# sch_microcontroller.net
KiCad netlist of a schematic drawn in EasyEDA
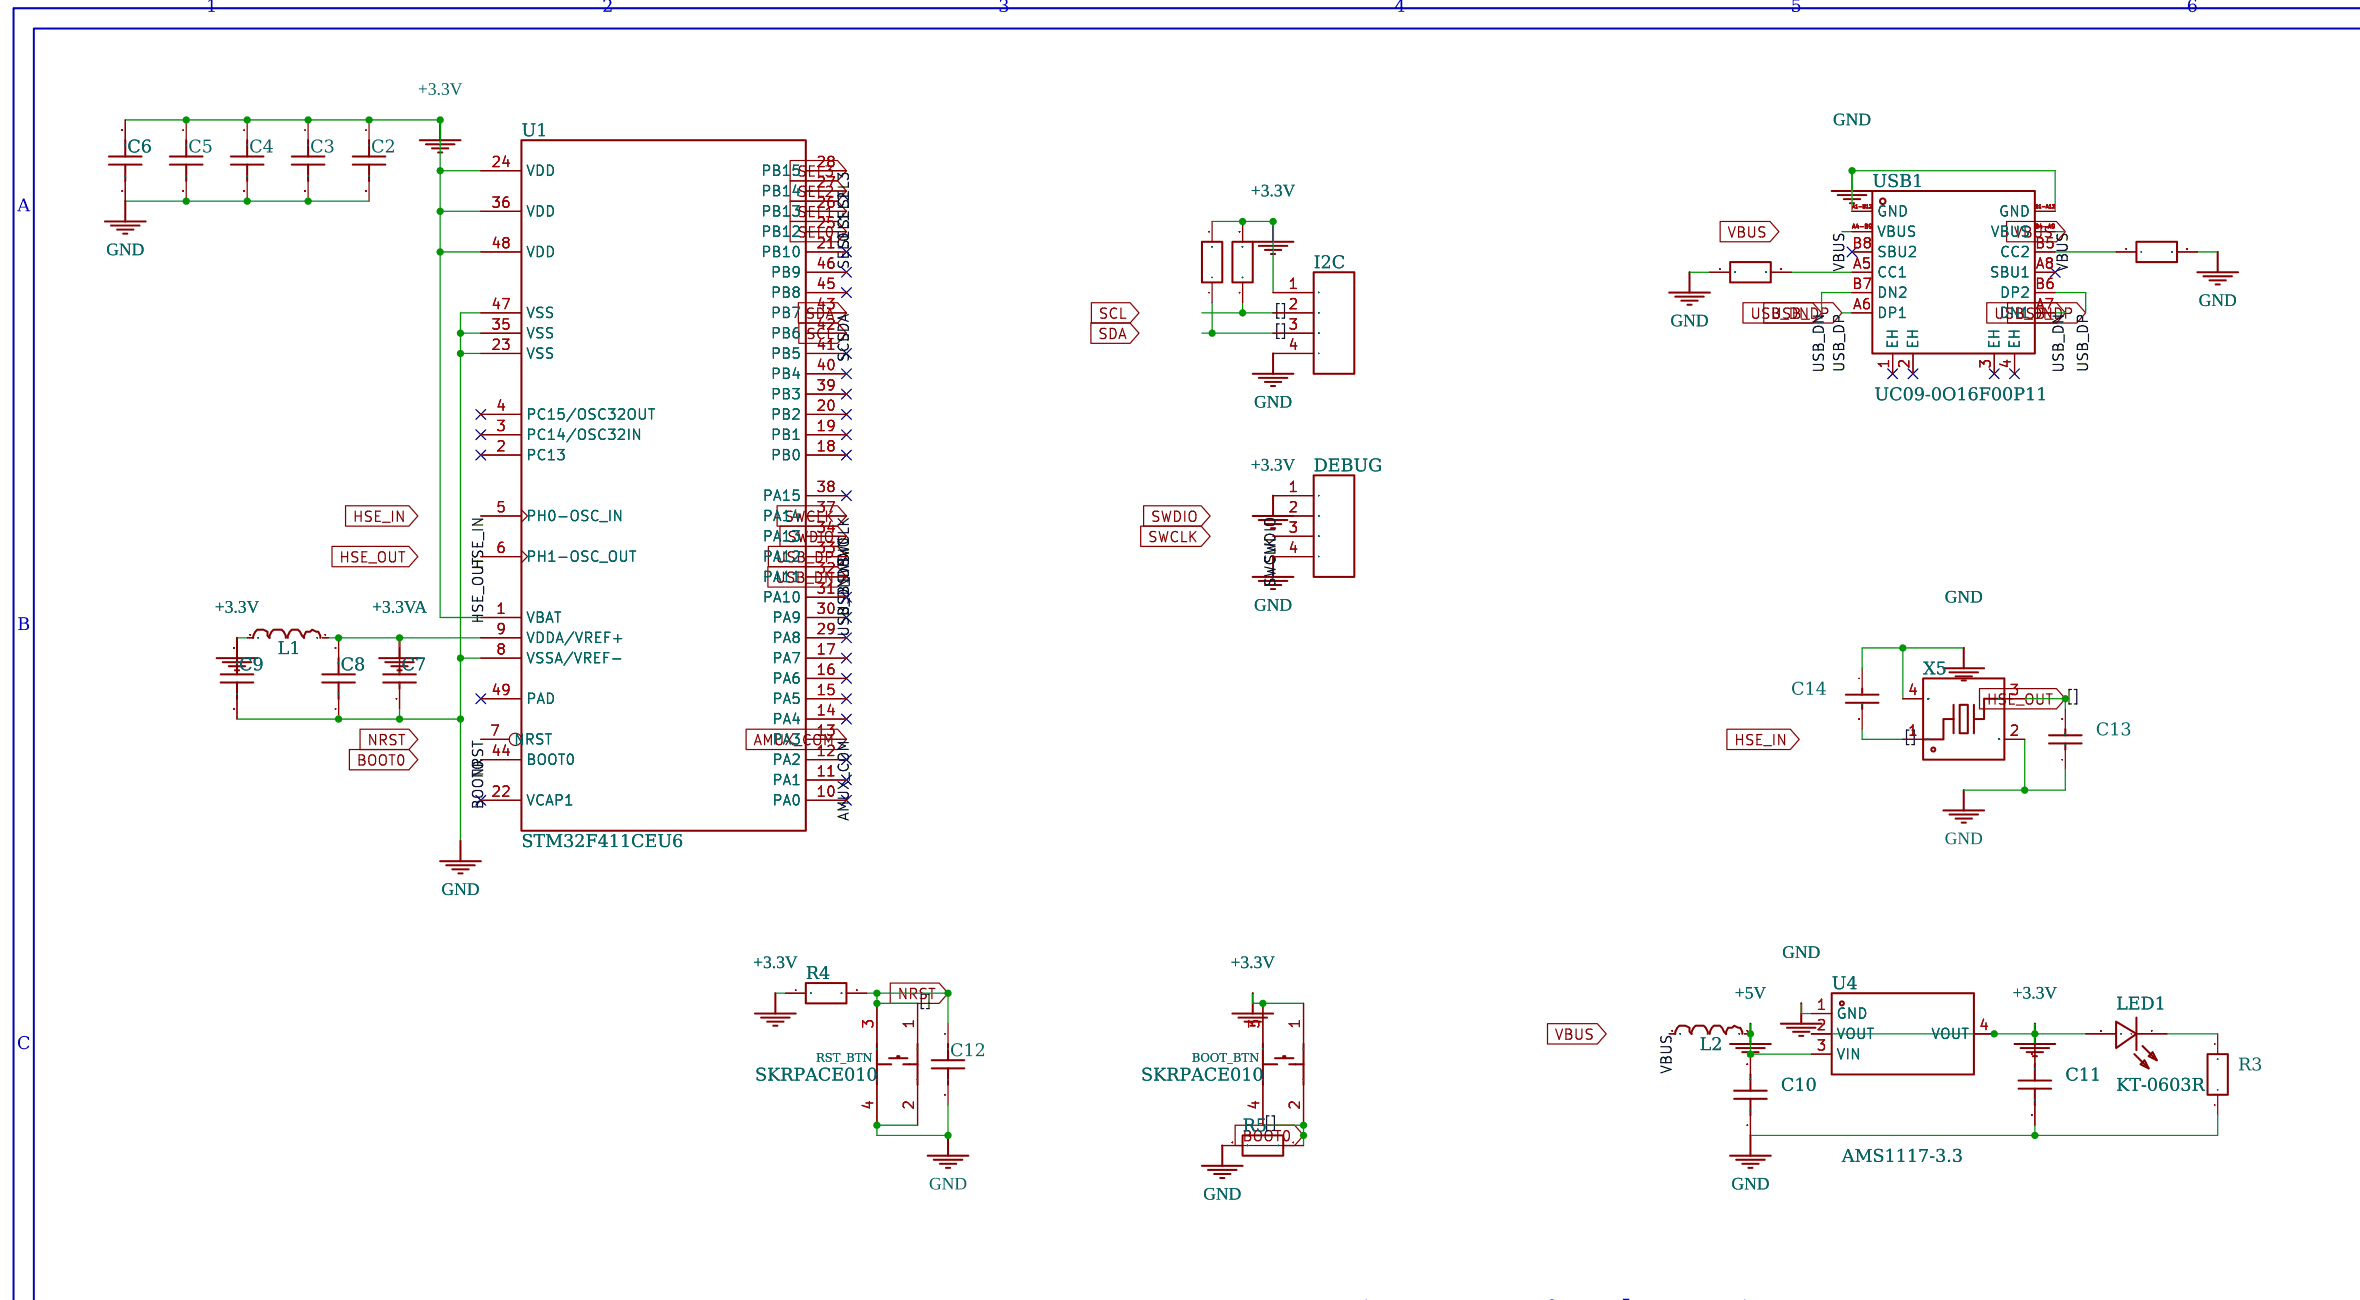
[diagram p0: schematic sheet]

(export (version "E")
  (design (tool "Eeschema 10.0.6"))
  (components
    (comp (ref "BOOT_BTN")
      (value "SKRPACE010")
      (fields (field (name "Manufacturer") "ALPSALPINE(阿尔卑斯阿尔派)"))
      (libsource (lib "") (part "Unknown_650_-325"))
    )
    (comp (ref "C2")
      (value "100nF")
      (fields
        (field (name "Manufacturer Part") "TCC0201X7R104K160ZT")
        (field (name "Manufacturer") "CCTC(三环)")
      )
      (libsource (lib "") (part "Unknown_195_-770"))
    )
    (comp (ref "C3")
      (value "100nF")
      (fields
        (field (name "Manufacturer Part") "TCC0201X7R104K160ZT")
        (field (name "Manufacturer") "CCTC(三环)")
      )
      (libsource (lib "") (part "Unknown_165_-770"))
    )
    (comp (ref "C4")
      (value "100nF")
      (fields
        (field (name "Manufacturer Part") "TCC0201X7R104K160ZT")
        (field (name "Manufacturer") "CCTC(三环)")
      )
      (libsource (lib "") (part "Unknown_135_-770"))
    )
    (comp (ref "C5")
      (value "100nF")
      (fields
        (field (name "Manufacturer Part") "TCC0201X7R104K160ZT")
        (field (name "Manufacturer") "CCTC(三环)")
      )
      (libsource (lib "") (part "Unknown_105_-770"))
    )
    (comp (ref "C6")
      (value "10uF")
      (fields
        (field (name "Manufacturer Part") "HGC1206R7106K350NSPJ")
        (field (name "Manufacturer") "Chinocera(华瓷)")
      )
      (libsource (lib "") (part "Unknown_75_-770"))
    )
    (comp (ref "C7")
      (value "10nF")
      (fields (field (name "Manufacturer Part") "0402B103K500NT") (field (name "Manufacturer") "FH(风华)"))
      (libsource (lib "") (part "Unknown_210_-515"))
    )
    (comp (ref "C8")
      (value "1uF")
      (fields
        (field (name "Manufacturer Part") "TCC0402X5R105K500AT")
        (field (name "Manufacturer") "CCTC(三环)")
      )
      (libsource (lib "") (part "Unknown_180_-515"))
    )
    (comp (ref "C9")
      (value "1uF")
      (fields
        (field (name "Manufacturer Part") "TCC0402X5R105K500AT")
        (field (name "Manufacturer") "CCTC(三环)")
      )
      (libsource (lib "") (part "Unknown_130_-515"))
    )
    (comp (ref "C10")
      (value "22uF")
      (fields
        (field (name "Manufacturer Part") "TCC1206X7R226K160HT")
        (field (name "Manufacturer") "CCTC(三环)")
      )
      (libsource (lib "") (part "Unknown_875_-310"))
    )
    (comp (ref "C11")
      (value "22uF")
      (fields
        (field (name "Manufacturer Part") "TCC1206X7R226K160HT")
        (field (name "Manufacturer") "CCTC(三环)")
      )
      (libsource (lib "") (part "Unknown_1015_-315"))
    )
    (comp (ref "C12")
      (value "100nF")
      (fields
        (field (name "Manufacturer Part") "TCC0201X7R104K160ZT")
        (field (name "Manufacturer") "CCTC(三环)")
      )
      (libsource (lib "") (part "Unknown_480_-325"))
    )
    (comp (ref "C13")
      (value "20pF")
      (fields (field (name "Manufacturer Part") "0402CG200J500NT") (field (name "Manufacturer") "FH(风华)"))
      (libsource (lib "") (part "Unknown_1030_-485"))
    )
    (comp (ref "C14")
      (value "20pF")
      (fields (field (name "Manufacturer Part") "0402CG200J500NT") (field (name "Manufacturer") "FH(风华)"))
      (libsource (lib "") (part "Unknown_930_-505"))
    )
    (comp (ref "DEBUG") (value "NO") (libsource (lib "") (part "Unknown_640_-595")))
    (comp (ref "I2C") (value "NO") (libsource (lib "") (part "Unknown_640_-695")))
    (comp (ref "L1")
      (value "BLM18AG121SN1D")
      (fields (field (name "Manufacturer") "muRata(村田)"))
      (libsource (lib "") (part "Unknown_155_-535"))
    )
    (comp (ref "L2")
      (value "BLM18AG121SN1D")
      (fields (field (name "Manufacturer") "muRata(村田)"))
      (libsource (lib "") (part "Unknown_855_-340"))
    )
    (comp (ref "LED1")
      (value "KT-0603R")
      (fields (field (name "Manufacturer") "KENTO"))
      (libsource (lib "") (part "Unknown_1060_-340"))
    )
    (comp (ref "R1")
      (value "5.1kΩ")
      (fields (field (name "Manufacturer Part") "FRC0402J512 TS") (field (name "Manufacturer") "FOJAN(富捷)"))
      (libsource (lib "") (part "Unknown_875_-715"))
    )
    (comp (ref "R2")
      (value "5.1kΩ")
      (fields (field (name "Manufacturer Part") "FRC0402J512 TS") (field (name "Manufacturer") "FOJAN(富捷)"))
      (libsource (lib "") (part "Unknown_1075_-725"))
    )
    (comp (ref "R3")
      (value "5.1kΩ")
      (fields (field (name "Manufacturer Part") "FRC0402J512 TS") (field (name "Manufacturer") "FOJAN(富捷)"))
      (libsource (lib "") (part "Unknown_1105_-320"))
    )
    (comp (ref "R4")
      (value "10kΩ")
      (fields
        (field (name "Manufacturer Part") "HoAR0805-1/8W-10KR-1%-TCR25")
        (field (name "Manufacturer") "Milliohm(毫欧)")
      )
      (libsource (lib "") (part "Unknown_420_-360"))
    )
    (comp (ref "R5")
      (value "10kΩ")
      (fields
        (field (name "Manufacturer Part") "HoAR0805-1/8W-10KR-1%-TCR25")
        (field (name "Manufacturer") "Milliohm(毫欧)")
      )
      (libsource (lib "") (part "Unknown_635_-285"))
    )
    (comp (ref "R6")
      (value "1.2kΩ")
      (fields (field (name "Manufacturer Part") "AC0201FR-071K2L") (field (name "Manufacturer") "YAGEO(国巨)"))
      (libsource (lib "") (part "Unknown_625_-720"))
    )
    (comp (ref "R7")
      (value "1.2kΩ")
      (fields (field (name "Manufacturer Part") "AC0201FR-071K2L") (field (name "Manufacturer") "YAGEO(国巨)"))
      (libsource (lib "") (part "Unknown_610_-720"))
    )
    (comp (ref "RST_BTN")
      (value "SKRPACE010")
      (fields (field (name "Manufacturer") "ALPSALPINE(阿尔卑斯阿尔派)"))
      (libsource (lib "") (part "Unknown_460_-325"))
    )
    (comp (ref "U1")
      (value "STM32F411CEU6")
      (fields (field (name "Manufacturer") "ST(意法半导体)"))
      (libsource (lib "") (part "Unknown_340_-605"))
    )
    (comp (ref "U4")
      (value "AMS1117-3.3")
      (fields (field (name "Manufacturer") "AMS"))
      (libsource (lib "") (part "Unknown_950_-340"))
    )
    (comp (ref "USB1")
      (value "UC09-0O16F00P11")
      (fields (field (name "Manufacturer") "BXCONN(宝讯)"))
      (libsource (lib "") (part "Unknown_975_-705"))
    )
    (comp (ref "X5")
      (value "25MHz")
      (fields (field (name "Manufacturer Part") "S3225000271060C3") (field (name "Manufacturer") "JGHC(晶光华)"))
      (libsource (lib "") (part "Unknown_980_-495"))
    )
  )
  (nets
    (net (code "1") (name "+3.3V") (class "Default")
      (node (ref "BOOT_BTN") (pin "1") (pinfunction "1_1") (pintype "unspecified"))
      (node (ref "BOOT_BTN") (pin "3") (pinfunction "3_3") (pintype "unspecified"))
      (node (ref "C11") (pin "2") (pinfunction "2_2") (pintype "unspecified"))
      (node (ref "C2") (pin "1") (pinfunction "1_1") (pintype "unspecified"))
      (node (ref "C3") (pin "1") (pinfunction "1_1") (pintype "unspecified"))
      (node (ref "C4") (pin "1") (pinfunction "1_1") (pintype "unspecified"))
      (node (ref "C5") (pin "1") (pinfunction "1_1") (pintype "unspecified"))
      (node (ref "C6") (pin "2") (pinfunction "2_2") (pintype "unspecified"))
      (node (ref "C9") (pin "2") (pinfunction "2_2") (pintype "unspecified"))
      (node (ref "DEBUG") (pin "1") (pinfunction "1_1") (pintype "unspecified"))
      (node (ref "I2C") (pin "1") (pinfunction "1_1") (pintype "unspecified"))
      (node (ref "L1") (pin "1") (pinfunction "1_1") (pintype "unspecified"))
      (node (ref "LED1") (pin "2") (pinfunction "A_2") (pintype "unspecified"))
      (node (ref "R4") (pin "1") (pinfunction "1_1") (pintype "unspecified"))
      (node (ref "R6") (pin "2") (pinfunction "2_2") (pintype "unspecified"))
      (node (ref "R7") (pin "2") (pinfunction "2_2") (pintype "unspecified"))
      (node (ref "U1") (pin "1") (pinfunction "VBAT_1") (pintype "unspecified"))
      (node (ref "U1") (pin "24") (pinfunction "VDD_24") (pintype "unspecified"))
      (node (ref "U1") (pin "36") (pinfunction "VDD_36") (pintype "unspecified"))
      (node (ref "U1") (pin "48") (pinfunction "VDD_48") (pintype "unspecified"))
      (node (ref "U4") (pin "2") (pinfunction "VOUT_2") (pintype "unspecified"))
      (node (ref "U4") (pin "4") (pinfunction "VOUT_4") (pintype "unspecified"))
    )
    (net (code "2") (name "+3.3VA") (class "Default")
      (node (ref "C7") (pin "2") (pinfunction "2_2") (pintype "unspecified"))
      (node (ref "C8") (pin "2") (pinfunction "2_2") (pintype "unspecified"))
      (node (ref "L1") (pin "2") (pinfunction "2_2") (pintype "unspecified"))
      (node (ref "U1") (pin "9") (pinfunction "VDDA/VREF+_9") (pintype "unspecified"))
    )
    (net (code "3") (name "+5V") (class "Default")
      (node (ref "C10") (pin "2") (pinfunction "2_2") (pintype "unspecified"))
      (node (ref "L2") (pin "2") (pinfunction "2_2") (pintype "unspecified"))
      (node (ref "U4") (pin "3") (pinfunction "VIN_3") (pintype "unspecified"))
    )
    (net (code "4") (name "AMUX_COM") (class "Default")
      (node (ref "U1") (pin "13") (pinfunction "PA3_13") (pintype "unspecified"))
    )
    (net (code "5") (name "BOOT0") (class "Default")
      (node (ref "BOOT_BTN") (pin "2") (pinfunction "2_2") (pintype "unspecified"))
      (node (ref "BOOT_BTN") (pin "4") (pinfunction "4_4") (pintype "unspecified"))
      (node (ref "C12") (pin "1") (pinfunction "1_1") (pintype "unspecified"))
      (node (ref "C13") (pin "2") (pinfunction "2_2") (pintype "unspecified"))
      (node (ref "C14") (pin "2") (pinfunction "2_2") (pintype "unspecified"))
      (node (ref "I2C") (pin "2") (pinfunction "2_2") (pintype "unspecified"))
      (node (ref "I2C") (pin "3") (pinfunction "3_3") (pintype "unspecified"))
      (node (ref "R4") (pin "2") (pinfunction "2_2") (pintype "unspecified"))
      (node (ref "R5") (pin "1") (pinfunction "1_1") (pintype "unspecified"))
      (node (ref "R6") (pin "1") (pinfunction "1_1") (pintype "unspecified"))
      (node (ref "R7") (pin "1") (pinfunction "1_1") (pintype "unspecified"))
      (node (ref "RST_BTN") (pin "1") (pinfunction "1_1") (pintype "unspecified"))
      (node (ref "RST_BTN") (pin "3") (pinfunction "3_3") (pintype "unspecified"))
      (node (ref "U1") (pin "44") (pinfunction "BOOT0_44") (pintype "unspecified"))
      (node (ref "U1") (pin "6") (pinfunction "PH1-OSC_OUT_6") (pintype "unspecified"))
      (node (ref "U1") (pin "7") (pinfunction "NRST_7") (pintype "unspecified"))
      (node (ref "X5") (pin "1") (pinfunction "1_1") (pintype "unspecified"))
      (node (ref "X5") (pin "3") (pinfunction "3_3") (pintype "unspecified"))
    )
    (net (code "6") (name "GND") (class "Default")
      (node (ref "C10") (pin "1") (pinfunction "1_1") (pintype "unspecified"))
      (node (ref "C11") (pin "1") (pinfunction "1_1") (pintype "unspecified"))
      (node (ref "C12") (pin "2") (pinfunction "2_2") (pintype "unspecified"))
      (node (ref "C13") (pin "1") (pinfunction "1_1") (pintype "unspecified"))
      (node (ref "C14") (pin "1") (pinfunction "1_1") (pintype "unspecified"))
      (node (ref "C2") (pin "2") (pinfunction "2_2") (pintype "unspecified"))
      (node (ref "C3") (pin "2") (pinfunction "2_2") (pintype "unspecified"))
      (node (ref "C4") (pin "2") (pinfunction "2_2") (pintype "unspecified"))
      (node (ref "C5") (pin "2") (pinfunction "2_2") (pintype "unspecified"))
      (node (ref "C6") (pin "1") (pinfunction "1_1") (pintype "unspecified"))
      (node (ref "C7") (pin "1") (pinfunction "1_1") (pintype "unspecified"))
      (node (ref "C8") (pin "1") (pinfunction "1_1") (pintype "unspecified"))
      (node (ref "C9") (pin "1") (pinfunction "1_1") (pintype "unspecified"))
      (node (ref "DEBUG") (pin "4") (pinfunction "4_4") (pintype "unspecified"))
      (node (ref "I2C") (pin "4") (pinfunction "4_4") (pintype "unspecified"))
      (node (ref "R1") (pin "1") (pinfunction "1_1") (pintype "unspecified"))
      (node (ref "R2") (pin "2") (pinfunction "2_2") (pintype "unspecified"))
      (node (ref "R3") (pin "1") (pinfunction "1_1") (pintype "unspecified"))
      (node (ref "R5") (pin "2") (pinfunction "2_2") (pintype "unspecified"))
      (node (ref "RST_BTN") (pin "2") (pinfunction "2_2") (pintype "unspecified"))
      (node (ref "RST_BTN") (pin "4") (pinfunction "4_4") (pintype "unspecified"))
      (node (ref "U1") (pin "23") (pinfunction "VSS_23") (pintype "unspecified"))
      (node (ref "U1") (pin "35") (pinfunction "VSS_35") (pintype "unspecified"))
      (node (ref "U1") (pin "47") (pinfunction "VSS_47") (pintype "unspecified"))
      (node (ref "U1") (pin "8") (pinfunction "VSSA/VREF-_8") (pintype "unspecified"))
      (node (ref "U4") (pin "1") (pinfunction "GND_1") (pintype "unspecified"))
      (node (ref "USB1") (pin "A1-B12") (pinfunction "GND_A1-B12") (pintype "unspecified"))
      (node (ref "USB1") (pin "B1-A12") (pinfunction "GND_B1-A12") (pintype "unspecified"))
      (node (ref "X5") (pin "2") (pinfunction "GND_2") (pintype "unspecified"))
      (node (ref "X5") (pin "4") (pinfunction "GND_4") (pintype "unspecified"))
    )
    (net (code "7") (name "HSE_IN") (class "Default")
      (node (ref "U1") (pin "5") (pinfunction "PH0-OSC_IN_5") (pintype "unspecified"))
    )
    (net (code "8") (name "Net-(LED1-K)") (class "Default")
      (node (ref "LED1") (pin "1") (pinfunction "K_1") (pintype "unspecified"))
      (node (ref "R3") (pin "2") (pinfunction "2_2") (pintype "unspecified"))
    )
    (net (code "9") (name "Net-(USB1-CC1)") (class "Default")
      (node (ref "R1") (pin "2") (pinfunction "2_2") (pintype "unspecified"))
      (node (ref "USB1") (pin "A5") (pinfunction "CC1_A5") (pintype "unspecified"))
    )
    (net (code "10") (name "Net-(USB1-CC2)") (class "Default")
      (node (ref "R2") (pin "1") (pinfunction "1_1") (pintype "unspecified"))
      (node (ref "USB1") (pin "B5") (pinfunction "CC2_B5") (pintype "unspecified"))
    )
    (net (code "11") (name "SCL") (class "Default")
      (node (ref "U1") (pin "42") (pinfunction "PB6_42") (pintype "unspecified"))
    )
    (net (code "12") (name "SDA") (class "Default")
      (node (ref "U1") (pin "43") (pinfunction "PB7_43") (pintype "unspecified"))
    )
    (net (code "13") (name "SEL0") (class "Default")
      (node (ref "U1") (pin "25") (pinfunction "PB12_25") (pintype "unspecified"))
    )
    (net (code "14") (name "SEL1") (class "Default")
      (node (ref "U1") (pin "26") (pinfunction "PB13_26") (pintype "unspecified"))
    )
    (net (code "15") (name "SEL2") (class "Default")
      (node (ref "U1") (pin "27") (pinfunction "PB14_27") (pintype "unspecified"))
    )
    (net (code "16") (name "SEL3") (class "Default")
      (node (ref "U1") (pin "28") (pinfunction "PB15_28") (pintype "unspecified"))
    )
    (net (code "17") (name "SWCLK") (class "Default")
      (node (ref "DEBUG") (pin "3") (pinfunction "3_3") (pintype "unspecified"))
      (node (ref "U1") (pin "37") (pinfunction "PA14_37") (pintype "unspecified"))
    )
    (net (code "18") (name "SWDIO") (class "Default")
      (node (ref "DEBUG") (pin "2") (pinfunction "2_2") (pintype "unspecified"))
      (node (ref "U1") (pin "34") (pinfunction "PA13_34") (pintype "unspecified"))
    )
    (net (code "19") (name "USB_DN") (class "Default")
      (node (ref "U1") (pin "32") (pinfunction "PA11_32") (pintype "unspecified"))
      (node (ref "USB1") (pin "A7") (pinfunction "DN1_A7") (pintype "unspecified"))
      (node (ref "USB1") (pin "B7") (pinfunction "DN2_B7") (pintype "unspecified"))
    )
    (net (code "20") (name "USB_DP") (class "Default")
      (node (ref "U1") (pin "33") (pinfunction "PA12_33") (pintype "unspecified"))
      (node (ref "USB1") (pin "A6") (pinfunction "DP1_A6") (pintype "unspecified"))
      (node (ref "USB1") (pin "B6") (pinfunction "DP2_B6") (pintype "unspecified"))
    )
    (net (code "21") (name "VBUS") (class "Default")
      (node (ref "L2") (pin "1") (pinfunction "1_1") (pintype "unspecified"))
      (node (ref "USB1") (pin "A4-B9") (pinfunction "VBUS_A4-B9") (pintype "unspecified"))
      (node (ref "USB1") (pin "B4-A9") (pinfunction "VBUS_B4-A9") (pintype "unspecified"))
    )
    (net (code "22") (name "unconnected-(U1-PA0-Pad10)") (class "Default")
      (node (ref "U1") (pin "10") (pinfunction "PA0_10") (pintype "unspecified+no_connect"))
    )
    (net (code "23") (name "unconnected-(U1-PA1-Pad11)") (class "Default")
      (node (ref "U1") (pin "11") (pinfunction "PA1_11") (pintype "unspecified+no_connect"))
    )
    (net (code "24") (name "unconnected-(U1-PA2-Pad12)") (class "Default")
      (node (ref "U1") (pin "12") (pinfunction "PA2_12") (pintype "unspecified+no_connect"))
    )
    (net (code "25") (name "unconnected-(U1-PA4-Pad14)") (class "Default")
      (node (ref "U1") (pin "14") (pinfunction "PA4_14") (pintype "unspecified+no_connect"))
    )
    (net (code "26") (name "unconnected-(U1-PA5-Pad15)") (class "Default")
      (node (ref "U1") (pin "15") (pinfunction "PA5_15") (pintype "unspecified+no_connect"))
    )
    (net (code "27") (name "unconnected-(U1-PA6-Pad16)") (class "Default")
      (node (ref "U1") (pin "16") (pinfunction "PA6_16") (pintype "unspecified+no_connect"))
    )
    (net (code "28") (name "unconnected-(U1-PA7-Pad17)") (class "Default")
      (node (ref "U1") (pin "17") (pinfunction "PA7_17") (pintype "unspecified+no_connect"))
    )
    (net (code "29") (name "unconnected-(U1-PA8-Pad29)") (class "Default")
      (node (ref "U1") (pin "29") (pinfunction "PA8_29") (pintype "unspecified+no_connect"))
    )
    (net (code "30") (name "unconnected-(U1-PA9-Pad30)") (class "Default")
      (node (ref "U1") (pin "30") (pinfunction "PA9_30") (pintype "unspecified+no_connect"))
    )
    (net (code "31") (name "unconnected-(U1-PA10-Pad31)") (class "Default")
      (node (ref "U1") (pin "31") (pinfunction "PA10_31") (pintype "unspecified+no_connect"))
    )
    (net (code "32") (name "unconnected-(U1-PA15-Pad38)") (class "Default")
      (node (ref "U1") (pin "38") (pinfunction "PA15_38") (pintype "unspecified+no_connect"))
    )
    (net (code "33") (name "unconnected-(U1-PAD-Pad49)") (class "Default")
      (node (ref "U1") (pin "49") (pinfunction "PAD_49") (pintype "unspecified+no_connect"))
    )
    (net (code "34") (name "unconnected-(U1-PB0-Pad18)") (class "Default")
      (node (ref "U1") (pin "18") (pinfunction "PB0_18") (pintype "unspecified+no_connect"))
    )
    (net (code "35") (name "unconnected-(U1-PB1-Pad19)") (class "Default")
      (node (ref "U1") (pin "19") (pinfunction "PB1_19") (pintype "unspecified+no_connect"))
    )
    (net (code "36") (name "unconnected-(U1-PB2-Pad20)") (class "Default")
      (node (ref "U1") (pin "20") (pinfunction "PB2_20") (pintype "unspecified+no_connect"))
    )
    (net (code "37") (name "unconnected-(U1-PB3-Pad39)") (class "Default")
      (node (ref "U1") (pin "39") (pinfunction "PB3_39") (pintype "unspecified+no_connect"))
    )
    (net (code "38") (name "unconnected-(U1-PB4-Pad40)") (class "Default")
      (node (ref "U1") (pin "40") (pinfunction "PB4_40") (pintype "unspecified+no_connect"))
    )
    (net (code "39") (name "unconnected-(U1-PB5-Pad41)") (class "Default")
      (node (ref "U1") (pin "41") (pinfunction "PB5_41") (pintype "unspecified+no_connect"))
    )
    (net (code "40") (name "unconnected-(U1-PB8-Pad45)") (class "Default")
      (node (ref "U1") (pin "45") (pinfunction "PB8_45") (pintype "unspecified+no_connect"))
    )
    (net (code "41") (name "unconnected-(U1-PB9-Pad46)") (class "Default")
      (node (ref "U1") (pin "46") (pinfunction "PB9_46") (pintype "unspecified+no_connect"))
    )
    (net (code "42") (name "unconnected-(U1-PB10-Pad21)") (class "Default")
      (node (ref "U1") (pin "21") (pinfunction "PB10_21") (pintype "unspecified+no_connect"))
    )
    (net (code "43") (name "unconnected-(U1-PC13-Pad2)") (class "Default")
      (node (ref "U1") (pin "2") (pinfunction "PC13_2") (pintype "unspecified+no_connect"))
    )
    (net (code "44") (name "unconnected-(U1-PC14{slash}OSC32IN-Pad3)") (class "Default")
      (node (ref "U1") (pin "3") (pinfunction "PC14/OSC32IN_3") (pintype "unspecified+no_connect"))
    )
    (net (code "45") (name "unconnected-(U1-PC15{slash}OSC32OUT-Pad4)") (class "Default")
      (node (ref "U1") (pin "4") (pinfunction "PC15/OSC32OUT_4") (pintype "unspecified+no_connect"))
    )
    (net (code "46") (name "unconnected-(U1-VCAP1-Pad22)") (class "Default")
      (node (ref "U1") (pin "22") (pinfunction "VCAP1_22") (pintype "unspecified+no_connect"))
    )
    (net (code "47") (name "unconnected-(USB1-EH-Pad1)") (class "Default")
      (node (ref "USB1") (pin "1") (pinfunction "EH_1") (pintype "unspecified+no_connect"))
    )
    (net (code "48") (name "unconnected-(USB1-EH-Pad2)") (class "Default")
      (node (ref "USB1") (pin "2") (pinfunction "EH_2") (pintype "unspecified+no_connect"))
    )
    (net (code "49") (name "unconnected-(USB1-EH-Pad3)") (class "Default")
      (node (ref "USB1") (pin "3") (pinfunction "EH_3") (pintype "unspecified+no_connect"))
    )
    (net (code "50") (name "unconnected-(USB1-EH-Pad4)") (class "Default")
      (node (ref "USB1") (pin "4") (pinfunction "EH_4") (pintype "unspecified+no_connect"))
    )
    (net (code "51") (name "unconnected-(USB1-SBU1-PadA8)") (class "Default")
      (node (ref "USB1") (pin "A8") (pinfunction "SBU1_A8") (pintype "unspecified+no_connect"))
    )
    (net (code "52") (name "unconnected-(USB1-SBU2-PadB8)") (class "Default")
      (node (ref "USB1") (pin "B8") (pinfunction "SBU2_B8") (pintype "unspecified+no_connect"))
    )
  )
)
